# 3dring.net
KiCad netlist of a schematic drawn in EAGLE
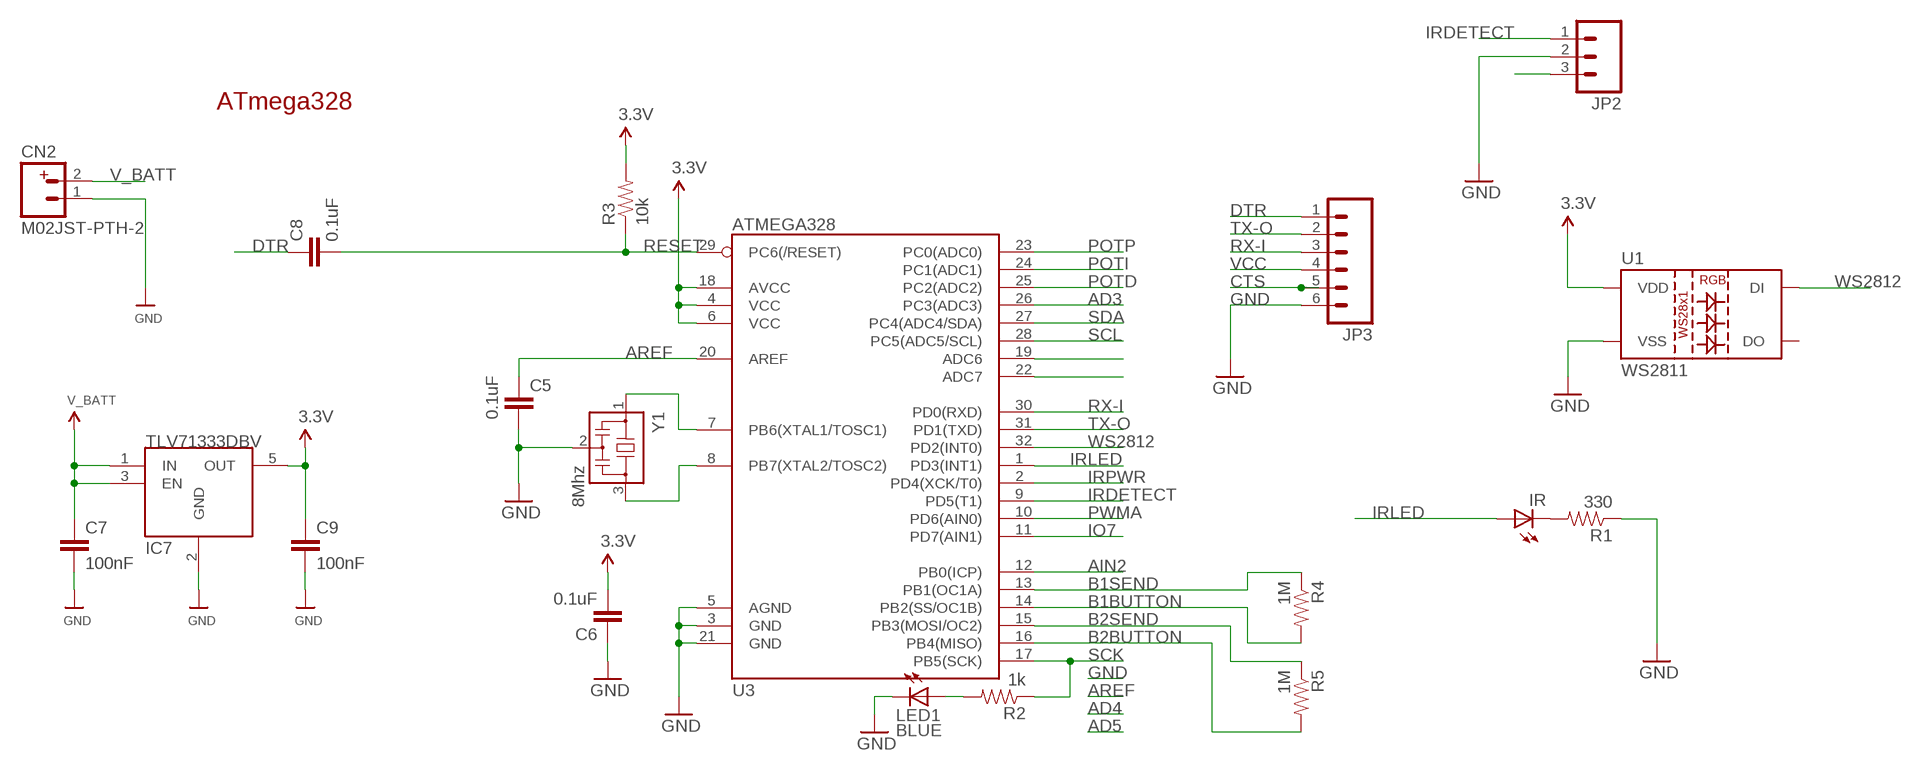
[diagram p0: schematic, sheet 1]

(export (version "E")
  (design (tool "Eeschema 10.0.6"))
  (components
    (comp (ref "C5")
      (value "0.1uF")
      (footprint "eagle-import:0402-CAP")
      (libsource (lib "eagle-import") (part "CAP0402-CAP"))
    )
    (comp (ref "C6")
      (value "0.1uF")
      (footprint "eagle-import:0402-CAP")
      (libsource (lib "eagle-import") (part "CAP0402-CAP"))
    )
    (comp (ref "C7")
      (value "100nF")
      (footprint "eagle-import:C0402")
      (libsource (lib "eagle-import") (part "C-EUC0402"))
    )
    (comp (ref "C8")
      (value "0.1uF")
      (footprint "eagle-import:0402-CAP")
      (libsource (lib "eagle-import") (part "CAP0402-CAP"))
    )
    (comp (ref "C9")
      (value "100nF")
      (footprint "eagle-import:C0402")
      (libsource (lib "eagle-import") (part "C-EUC0402"))
    )
    (comp (ref "CN2")
      (value "M02JST-PTH-2")
      (footprint "eagle-import:JST-2-PTH")
      (libsource (lib "eagle-import") (part "M02JST-PTH-2"))
    )
    (comp (ref "IC7")
      (value "TLV71333DBV")
      (footprint "eagle-import:SOT-23-5")
      (libsource (lib "eagle-import") (part "TLV713DBV33"))
    )
    (comp (ref "IR")
      (value "LED5MM")
      (footprint "eagle-import:LED5MM")
      (libsource (lib "eagle-import") (part "SparkFun-LED_LED5MM"))
    )
    (comp (ref "JP2")
      (value "M03PTH")
      (footprint "eagle-import:1X03")
      (libsource (lib "eagle-import") (part "M03PTH"))
    )
    (comp (ref "JP3")
      (value "M06SMD-1MM")
      (footprint "eagle-import:1X06-1MM")
      (libsource (lib "eagle-import") (part "M06SMD-1MM"))
    )
    (comp (ref "LED1")
      (value "BLUE")
      (footprint "eagle-import:LED-0603")
      (libsource (lib "eagle-import") (part "LED0603"))
    )
    (comp (ref "R1")
      (value "330")
      (footprint "eagle-import:0402-RES")
      (libsource (lib "eagle-import") (part "RESISTOR0402-RES"))
    )
    (comp (ref "R2")
      (value "1k")
      (footprint "eagle-import:0402-RES")
      (libsource (lib "eagle-import") (part "RESISTOR0402-RES"))
    )
    (comp (ref "R3")
      (value "10k")
      (footprint "eagle-import:0402-RES")
      (libsource (lib "eagle-import") (part "RESISTOR0402-RES"))
    )
    (comp (ref "R4")
      (value "1M")
      (footprint "eagle-import:0402-RES")
      (libsource (lib "eagle-import") (part "RESISTOR0402-RES"))
    )
    (comp (ref "R5")
      (value "1M")
      (footprint "eagle-import:0402-RES")
      (libsource (lib "eagle-import") (part "RESISTOR0402-RES"))
    )
    (comp (ref "U1")
      (value "WS2811")
      (footprint "eagle-import:LED-TRICOLOR-5050-IC")
      (libsource (lib "eagle-import") (part "LED-TRICOLOR-5050-ICWS2811"))
    )
    (comp (ref "U3")
      (value "ATMEGA328")
      (footprint "eagle-import:TQFP32-08")
      (libsource (lib "eagle-import") (part "ATMEGA168"))
    )
    (comp (ref "Y1")
      (value "8Mhz")
      (footprint "eagle-import:CSTCR6M")
      (fields (field (name "MPN") "CSTCR6M00G53-R0"))
      (libsource (lib "eagle-import") (part "CSTCR6M00G53Z"))
    )
  )
  (nets
    (net (code "1") (name "/AD3") (class "Default")
      (node (ref "U3") (pin "26") (pinfunction "PC3(ADC3)_26") (pintype "bidirectional"))
    )
    (net (code "4") (name "/AIN2") (class "Default")
      (node (ref "U3") (pin "12") (pinfunction "PB0(ICP)_12") (pintype "bidirectional"))
    )
    (net (code "5") (name "/AREF") (class "Default")
      (node (ref "C5") (pin "1") (pinfunction "1_1") (pintype "passive"))
      (node (ref "U3") (pin "20") (pinfunction "AREF_20") (pintype "bidirectional"))
    )
    (net (code "6") (name "/B1BUTTON") (class "Default")
      (node (ref "R4") (pin "2") (pinfunction "2_2") (pintype "passive"))
      (node (ref "U3") (pin "14") (pinfunction "PB2(SS/OC1B)_14") (pintype "bidirectional"))
    )
    (net (code "7") (name "/B1SEND") (class "Default")
      (node (ref "R4") (pin "1") (pinfunction "1_1") (pintype "passive"))
      (node (ref "U3") (pin "13") (pinfunction "PB1(OC1A)_13") (pintype "bidirectional"))
    )
    (net (code "8") (name "/B2BUTTON") (class "Default")
      (node (ref "R5") (pin "2") (pinfunction "2_2") (pintype "passive"))
      (node (ref "U3") (pin "16") (pinfunction "PB4(MISO)_16") (pintype "bidirectional"))
    )
    (net (code "9") (name "/B2SEND") (class "Default")
      (node (ref "R5") (pin "1") (pinfunction "1_1") (pintype "passive"))
      (node (ref "U3") (pin "15") (pinfunction "PB3(MOSI/OC2)_15") (pintype "bidirectional"))
    )
    (net (code "10") (name "/CTS") (class "Default")
      (node (ref "JP3") (pin "5") (pinfunction "5_5") (pintype "passive"))
    )
    (net (code "11") (name "/DTR") (class "Default")
      (node (ref "C8") (pin "1") (pinfunction "1_1") (pintype "passive"))
      (node (ref "JP3") (pin "1") (pinfunction "1_1") (pintype "passive"))
    )
    (net (code "12") (name "/IO7") (class "Default")
      (node (ref "U3") (pin "11") (pinfunction "PD7(AIN1)_11") (pintype "bidirectional"))
    )
    (net (code "13") (name "/IRDETECT") (class "Default")
      (node (ref "JP2") (pin "1") (pinfunction "1_1") (pintype "passive"))
      (node (ref "U3") (pin "9") (pinfunction "PD5(T1)_9") (pintype "bidirectional"))
    )
    (net (code "14") (name "/IRLED") (class "Default")
      (node (ref "IR") (pin "A") (pinfunction "A_A") (pintype "passive"))
      (node (ref "U3") (pin "1") (pinfunction "PD3(INT1)_1") (pintype "bidirectional"))
    )
    (net (code "15") (name "/IRPWR") (class "Default")
      (node (ref "JP2") (pin "3") (pinfunction "3_3") (pintype "passive"))
      (node (ref "U3") (pin "2") (pinfunction "PD4(XCK/T0)_2") (pintype "bidirectional"))
    )
    (net (code "16") (name "/POTD") (class "Default")
      (node (ref "U3") (pin "25") (pinfunction "PC2(ADC2)_25") (pintype "bidirectional"))
    )
    (net (code "17") (name "/POTI") (class "Default")
      (node (ref "U3") (pin "24") (pinfunction "PC1(ADC1)_24") (pintype "bidirectional"))
    )
    (net (code "18") (name "/POTP") (class "Default")
      (node (ref "U3") (pin "23") (pinfunction "PC0(ADC0)_23") (pintype "bidirectional"))
    )
    (net (code "19") (name "/PWMA") (class "Default")
      (node (ref "U3") (pin "10") (pinfunction "PD6(AIN0)_10") (pintype "bidirectional"))
    )
    (net (code "20") (name "/RESET") (class "Default")
      (node (ref "C8") (pin "2") (pinfunction "2_2") (pintype "passive"))
      (node (ref "R3") (pin "1") (pinfunction "1_1") (pintype "passive"))
      (node (ref "U3") (pin "29") (pinfunction "PC6(/RESET)_29") (pintype "bidirectional"))
    )
    (net (code "21") (name "/RX-I") (class "Default")
      (node (ref "JP3") (pin "3") (pinfunction "3_3") (pintype "passive"))
      (node (ref "U3") (pin "30") (pinfunction "PD0(RXD)_30") (pintype "bidirectional"))
    )
    (net (code "22") (name "/SCK") (class "Default")
      (node (ref "R2") (pin "1") (pinfunction "1_1") (pintype "passive"))
      (node (ref "U3") (pin "17") (pinfunction "PB5(SCK)_17") (pintype "bidirectional"))
    )
    (net (code "23") (name "/SCL") (class "Default")
      (node (ref "U3") (pin "28") (pinfunction "PC5(ADC5/SCL)_28") (pintype "bidirectional"))
    )
    (net (code "24") (name "/SDA") (class "Default")
      (node (ref "U3") (pin "27") (pinfunction "PC4(ADC4/SDA)_27") (pintype "bidirectional"))
    )
    (net (code "25") (name "/TX-O") (class "Default")
      (node (ref "JP3") (pin "2") (pinfunction "2_2") (pintype "passive"))
      (node (ref "U3") (pin "31") (pinfunction "PD1(TXD)_31") (pintype "bidirectional"))
    )
    (net (code "26") (name "/WS2812") (class "Default")
      (node (ref "U1") (pin "2") (pinfunction "DI_2") (pintype "bidirectional"))
      (node (ref "U3") (pin "32") (pinfunction "PD2(INT0)_32") (pintype "bidirectional"))
    )
    (net (code "27") (name "3.3V") (class "Default")
      (node (ref "C6") (pin "2") (pinfunction "2_2") (pintype "passive"))
      (node (ref "C9") (pin "1") (pinfunction "1_1") (pintype "passive"))
      (node (ref "IC7") (pin "5") (pinfunction "OUT_5") (pintype "power_in"))
      (node (ref "JP3") (pin "4") (pinfunction "4_4") (pintype "passive"))
      (node (ref "R3") (pin "2") (pinfunction "2_2") (pintype "passive"))
      (node (ref "U1") (pin "3") (pinfunction "VDD_3") (pintype "bidirectional"))
      (node (ref "U1") (pin "5") (pinfunction "VDD_5") (pintype "bidirectional"))
      (node (ref "U3") (pin "18") (pinfunction "AVCC_18") (pintype "bidirectional"))
      (node (ref "U3") (pin "4") (pinfunction "VCC_4") (pintype "bidirectional"))
      (node (ref "U3") (pin "6") (pinfunction "VCC_6") (pintype "bidirectional"))
    )
    (net (code "28") (name "GND") (class "Default")
      (node (ref "C5") (pin "2") (pinfunction "2_2") (pintype "passive"))
      (node (ref "C6") (pin "1") (pinfunction "1_1") (pintype "passive"))
      (node (ref "C7") (pin "2") (pinfunction "2_2") (pintype "passive"))
      (node (ref "C9") (pin "2") (pinfunction "2_2") (pintype "passive"))
      (node (ref "CN2") (pin "1") (pinfunction "1_1") (pintype "passive"))
      (node (ref "IC7") (pin "2") (pinfunction "GND_2") (pintype "power_in"))
      (node (ref "JP2") (pin "2") (pinfunction "2_2") (pintype "passive"))
      (node (ref "JP3") (pin "6") (pinfunction "6_6") (pintype "passive"))
      (node (ref "LED1") (pin "C") (pinfunction "C_C") (pintype "passive"))
      (node (ref "R1") (pin "1") (pinfunction "1_1") (pintype "passive"))
      (node (ref "U1") (pin "6") (pinfunction "VSS_6") (pintype "bidirectional"))
      (node (ref "U3") (pin "21") (pinfunction "GND_21") (pintype "bidirectional"))
      (node (ref "U3") (pin "3") (pinfunction "GND_3") (pintype "bidirectional"))
      (node (ref "U3") (pin "5") (pinfunction "AGND_5") (pintype "bidirectional"))
      (node (ref "Y1") (pin "2") (pinfunction "2_2") (pintype "passive"))
    )
    (net (code "29") (name "Net-(IR-C)") (class "Default")
      (node (ref "IR") (pin "K") (pinfunction "C_K") (pintype "passive"))
      (node (ref "R1") (pin "2") (pinfunction "2_2") (pintype "passive"))
    )
    (net (code "30") (name "Net-(LED1-PadA)") (class "Default")
      (node (ref "LED1") (pin "A") (pinfunction "A_A") (pintype "passive"))
      (node (ref "R2") (pin "2") (pinfunction "2_2") (pintype "passive"))
    )
    (net (code "31") (name "Net-(U3-PB6(XTAL1{slash}TOSC1))") (class "Default")
      (node (ref "U3") (pin "7") (pinfunction "PB6(XTAL1/TOSC1)_7") (pintype "bidirectional"))
      (node (ref "Y1") (pin "1") (pinfunction "1_1") (pintype "passive"))
    )
    (net (code "32") (name "Net-(U3-PB7(XTAL2{slash}TOSC2))") (class "Default")
      (node (ref "U3") (pin "8") (pinfunction "PB7(XTAL2/TOSC2)_8") (pintype "bidirectional"))
      (node (ref "Y1") (pin "3") (pinfunction "3_3") (pintype "passive"))
    )
    (net (code "33") (name "V_BATT") (class "Default")
      (node (ref "C7") (pin "1") (pinfunction "1_1") (pintype "passive"))
      (node (ref "CN2") (pin "2") (pinfunction "2_2") (pintype "passive"))
      (node (ref "IC7") (pin "1") (pinfunction "IN_1") (pintype "power_in"))
      (node (ref "IC7") (pin "3") (pinfunction "EN_3") (pintype "input"))
    )
    (net (code "34") (name "unconnected-(U1-DO-Pad1)") (class "Default")
      (node (ref "U1") (pin "1") (pinfunction "DO_1") (pintype "bidirectional"))
    )
    (net (code "35") (name "unconnected-(U3-ADC6-Pad19)") (class "Default")
      (node (ref "U3") (pin "19") (pinfunction "ADC6_19") (pintype "bidirectional"))
    )
    (net (code "36") (name "unconnected-(U3-ADC7-Pad22)") (class "Default")
      (node (ref "U3") (pin "22") (pinfunction "ADC7_22") (pintype "bidirectional"))
    )
  )
)
